# charger.net
KiCad netlist of a schematic drawn in EAGLE
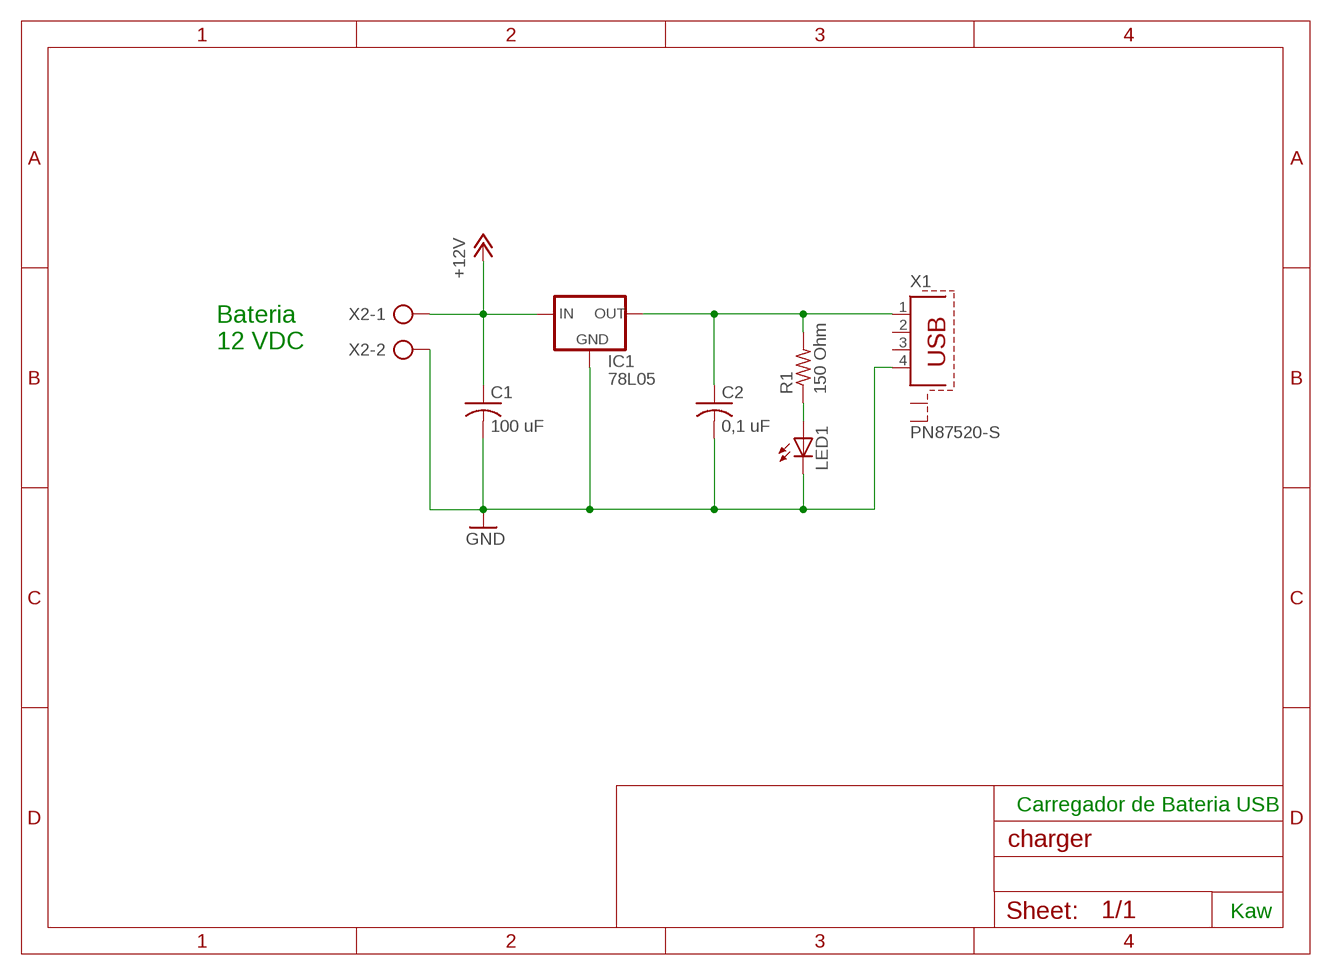
[diagram p0: schematic, sheet 1]

(export (version "E")
  (design (tool "Eeschema 10.0.6"))
  (components
    (comp (ref "C1")
      (value "100 uF")
      (footprint "eagle-import:C025-025X050")
      (libsource (lib "eagle-import") (part "C-US025-025X050"))
    )
    (comp (ref "C2")
      (value "0,1 uF")
      (footprint "eagle-import:C025-025X050")
      (libsource (lib "eagle-import") (part "C-US025-025X050"))
    )
    (comp (ref "IC1")
      (value "78L05")
      (footprint "eagle-import:78XXS")
      (libsource (lib "eagle-import") (part "78XXS"))
    )
    (comp (ref "LED1")
      (value "LED5MM")
      (footprint "eagle-import:LED5MM")
      (libsource (lib "eagle-import") (part "LED5MM"))
    )
    (comp (ref "R1")
      (value "150 Ohm")
      (footprint "eagle-import:0207_5V")
      (libsource (lib "eagle-import") (part "R-US_0207/5V"))
    )
    (comp (ref "X1")
      (value "PN87520-S")
      (footprint "eagle-import:PN87520-S")
      (libsource (lib "eagle-import") (part "PN87520-S"))
    )
    (comp (ref "X2")
      (value "AK300/2")
      (footprint "eagle-import:AK300_2")
      (libsource (lib "eagle-import") (part "AK300/2"))
    )
  )
  (nets
    (net (code "1") (name "+12V") (class "Default")
      (node (ref "C1") (pin "1") (pinfunction "1_1") (pintype "passive"))
      (node (ref "IC1") (pin "IN") (pinfunction "IN_IN") (pintype "input"))
      (node (ref "X2") (pin "1") (pinfunction "KL_1") (pintype "passive"))
    )
    (net (code "2") (name "GND") (class "Default")
      (node (ref "C1") (pin "2") (pinfunction "2_2") (pintype "passive"))
      (node (ref "C2") (pin "2") (pinfunction "2_2") (pintype "passive"))
      (node (ref "IC1") (pin "GND") (pinfunction "GND_GND") (pintype "input"))
      (node (ref "LED1") (pin "K") (pinfunction "C_K") (pintype "passive"))
      (node (ref "X1") (pin "4") (pinfunction "4_4") (pintype "passive"))
      (node (ref "X2") (pin "2") (pinfunction "KL_2") (pintype "passive"))
    )
    (net (code "3") (name "Net-(C2-Pad1)") (class "Default")
      (node (ref "C2") (pin "1") (pinfunction "1_1") (pintype "passive"))
      (node (ref "IC1") (pin "OUT") (pinfunction "OUT_OUT") (pintype "passive"))
      (node (ref "R1") (pin "2") (pinfunction "2_2") (pintype "passive"))
      (node (ref "X1") (pin "1") (pinfunction "1_1") (pintype "passive"))
    )
    (net (code "4") (name "Net-(LED1-PadA)") (class "Default")
      (node (ref "LED1") (pin "A") (pinfunction "A_A") (pintype "passive"))
      (node (ref "R1") (pin "1") (pinfunction "1_1") (pintype "passive"))
    )
    (net (code "5") (name "unconnected-(X1-Pad2)") (class "Default")
      (node (ref "X1") (pin "2") (pinfunction "2_2") (pintype "passive"))
    )
    (net (code "6") (name "unconnected-(X1-Pad3)") (class "Default")
      (node (ref "X1") (pin "3") (pinfunction "3_3") (pintype "passive"))
    )
    (net (code "7") (name "unconnected-(X1-PadS1)") (class "Default")
      (node (ref "X1") (pin "S1") (pinfunction "S1_S1") (pintype "passive"))
    )
    (net (code "8") (name "unconnected-(X1-PadS2)") (class "Default")
      (node (ref "X1") (pin "S2") (pinfunction "S2_S2") (pintype "passive"))
    )
  )
)
